# Wifi_Circuit.net
KiCad netlist of a schematic drawn in EAGLE
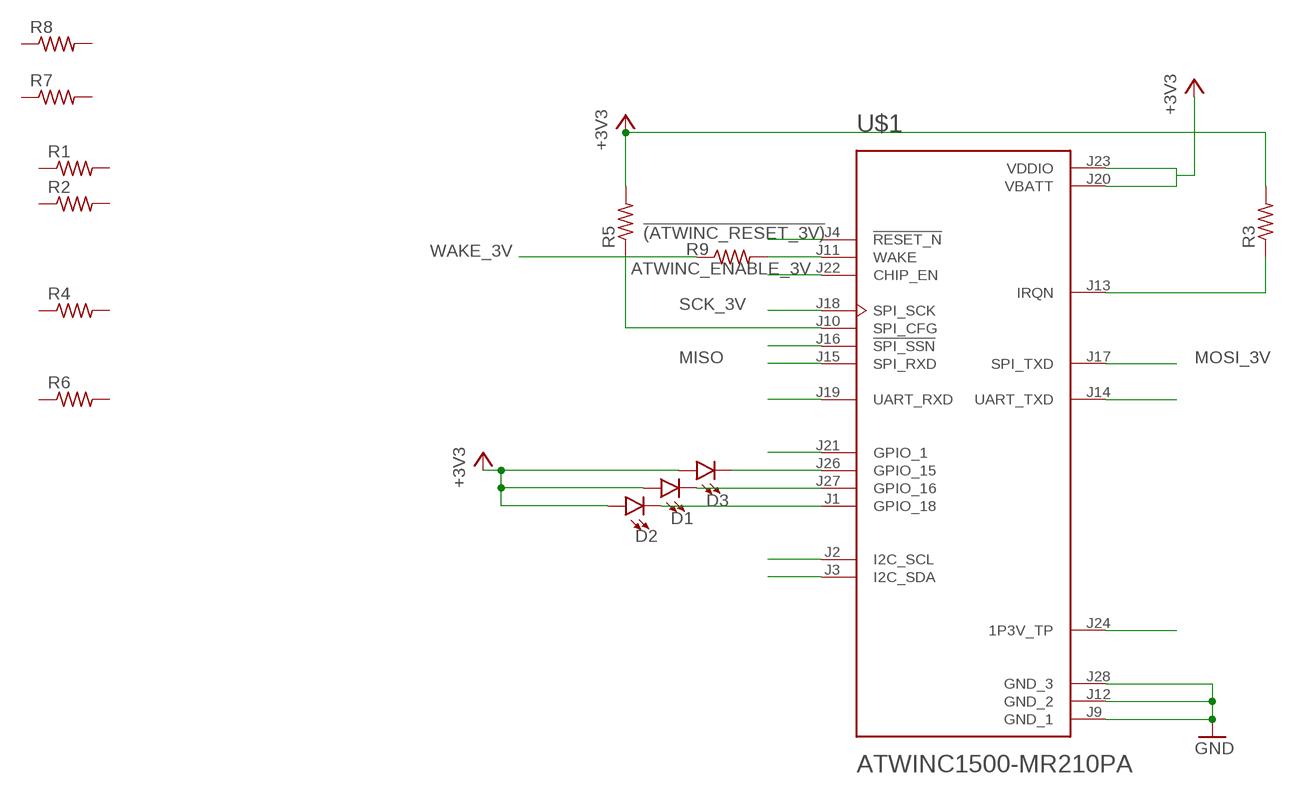
[diagram p0: schematic, sheet 1]

(export (version "E")
  (design (tool "Eeschema 10.0.6"))
  (components
    (comp (ref "D1")
      (value "LED3MM")
      (footprint "eagle-import:LED_3MM")
      (libsource (lib "eagle-import") (part "LED3MM"))
    )
    (comp (ref "D2")
      (value "LED3MM")
      (footprint "eagle-import:LED_3MM")
      (libsource (lib "eagle-import") (part "LED3MM"))
    )
    (comp (ref "D3")
      (value "LED3MM")
      (footprint "eagle-import:LED_3MM")
      (libsource (lib "eagle-import") (part "LED3MM"))
    )
    (comp (ref "R1")
      (value "R-US_R0805")
      (footprint "eagle-import:R0805")
      (libsource (lib "eagle-import") (part "R-US_R0805"))
    )
    (comp (ref "R2")
      (value "R-US_R0805")
      (footprint "eagle-import:R0805")
      (libsource (lib "eagle-import") (part "R-US_R0805"))
    )
    (comp (ref "R3")
      (value "R-US_R0805")
      (footprint "eagle-import:R0805")
      (libsource (lib "eagle-import") (part "R-US_R0805"))
    )
    (comp (ref "R4")
      (value "R-US_R0805")
      (footprint "eagle-import:R0805")
      (libsource (lib "eagle-import") (part "R-US_R0805"))
    )
    (comp (ref "R5")
      (value "R-US_R0805")
      (footprint "eagle-import:R0805")
      (libsource (lib "eagle-import") (part "R-US_R0805"))
    )
    (comp (ref "R6")
      (value "R-US_R0805")
      (footprint "eagle-import:R0805")
      (libsource (lib "eagle-import") (part "R-US_R0805"))
    )
    (comp (ref "R7")
      (value "R-US_R0805")
      (footprint "eagle-import:R0805")
      (libsource (lib "eagle-import") (part "R-US_R0805"))
    )
    (comp (ref "R8")
      (value "R-US_R0805")
      (footprint "eagle-import:R0805")
      (libsource (lib "eagle-import") (part "R-US_R0805"))
    )
    (comp (ref "R9")
      (value "R-US_R0805")
      (footprint "eagle-import:R0805")
      (libsource (lib "eagle-import") (part "R-US_R0805"))
    )
    (comp (ref "U$1")
      (value "ATWINC1500-MR210PA")
      (footprint "eagle-import:ATMEL_ATWINC1500-MR210PA")
      (fields (field (name "MF") "Microchip Technology"))
      (libsource (lib "eagle-import") (part "ATWINC1500-MR210PA"))
    )
  )
  (nets
    (net (code "1") (name "+3V3") (class "Default")
      (node (ref "D1") (pin "A") (pinfunction "A_A") (pintype "passive"))
      (node (ref "D2") (pin "A") (pinfunction "A_A") (pintype "passive"))
      (node (ref "D3") (pin "A") (pinfunction "A_A") (pintype "passive"))
      (node (ref "R3") (pin "2") (pinfunction "2_2") (pintype "passive"))
      (node (ref "R5") (pin "2") (pinfunction "2_2") (pintype "passive"))
      (node (ref "U$1") (pin "J20") (pinfunction "VBATT_J20") (pintype "power_in"))
      (node (ref "U$1") (pin "J23") (pinfunction "VDDIO_J23") (pintype "power_in"))
    )
    (net (code "2") (name "/ATWINC_ENABLE_3V") (class "Default")
      (node (ref "U$1") (pin "J22") (pinfunction "CHIP_EN_J22") (pintype "input"))
    )
    (net (code "3") (name "/MISO") (class "Default")
      (node (ref "U$1") (pin "J15") (pinfunction "SPI_RXD_J15") (pintype "input"))
    )
    (net (code "4") (name "/MOSI_3V") (class "Default")
      (node (ref "U$1") (pin "J17") (pinfunction "SPI_TXD_J17") (pintype "output"))
    )
    (net (code "5") (name "/SCK_3V") (class "Default")
      (node (ref "U$1") (pin "J18") (pinfunction "SPI_SCK_J18") (pintype "input"))
    )
    (net (code "6") (name "/WAKE_3V") (class "Default")
      (node (ref "R9") (pin "1") (pinfunction "1_1") (pintype "passive"))
    )
    (net (code "7") (name "/~{(ATWINC_RESET_3V})") (class "Default")
      (node (ref "U$1") (pin "J4") (pinfunction "~{RESET_N}_J4") (pintype "input"))
    )
    (net (code "8") (name "GND") (class "Default")
      (node (ref "U$1") (pin "J12") (pinfunction "GND_2_J12") (pintype "passive"))
      (node (ref "U$1") (pin "J28") (pinfunction "GND_3_J28") (pintype "passive"))
      (node (ref "U$1") (pin "J9") (pinfunction "GND_1_J9") (pintype "passive"))
    )
    (net (code "9") (name "Net-(D1-C)") (class "Default")
      (node (ref "D1") (pin "K") (pinfunction "C_K") (pintype "passive"))
      (node (ref "U$1") (pin "J27") (pinfunction "GPIO_16_J27") (pintype "bidirectional"))
    )
    (net (code "10") (name "Net-(D2-C)") (class "Default")
      (node (ref "D2") (pin "K") (pinfunction "C_K") (pintype "passive"))
      (node (ref "U$1") (pin "J1") (pinfunction "GPIO_18_J1") (pintype "bidirectional"))
    )
    (net (code "11") (name "Net-(D3-C)") (class "Default")
      (node (ref "D3") (pin "K") (pinfunction "C_K") (pintype "passive"))
      (node (ref "U$1") (pin "J26") (pinfunction "GPIO_15_J26") (pintype "bidirectional"))
    )
    (net (code "12") (name "Net-(U$1-IRQN)") (class "Default")
      (node (ref "R3") (pin "1") (pinfunction "1_1") (pintype "passive"))
      (node (ref "U$1") (pin "J13") (pinfunction "IRQN_J13") (pintype "output"))
    )
    (net (code "13") (name "Net-(U$1-SPI_CFG)") (class "Default")
      (node (ref "R5") (pin "1") (pinfunction "1_1") (pintype "passive"))
      (node (ref "U$1") (pin "J10") (pinfunction "SPI_CFG_J10") (pintype "input"))
    )
    (net (code "14") (name "Net-(U$1-WAKE)") (class "Default")
      (node (ref "R9") (pin "2") (pinfunction "2_2") (pintype "passive"))
      (node (ref "U$1") (pin "J11") (pinfunction "WAKE_J11") (pintype "input"))
    )
    (net (code "15") (name "unconnected-(R1-Pad1)") (class "Default")
      (node (ref "R1") (pin "1") (pinfunction "1_1") (pintype "passive"))
    )
    (net (code "16") (name "unconnected-(R1-Pad2)") (class "Default")
      (node (ref "R1") (pin "2") (pinfunction "2_2") (pintype "passive"))
    )
    (net (code "17") (name "unconnected-(R2-Pad1)") (class "Default")
      (node (ref "R2") (pin "1") (pinfunction "1_1") (pintype "passive"))
    )
    (net (code "18") (name "unconnected-(R2-Pad2)") (class "Default")
      (node (ref "R2") (pin "2") (pinfunction "2_2") (pintype "passive"))
    )
    (net (code "19") (name "unconnected-(R4-Pad1)") (class "Default")
      (node (ref "R4") (pin "1") (pinfunction "1_1") (pintype "passive"))
    )
    (net (code "20") (name "unconnected-(R4-Pad2)") (class "Default")
      (node (ref "R4") (pin "2") (pinfunction "2_2") (pintype "passive"))
    )
    (net (code "21") (name "unconnected-(R6-Pad1)") (class "Default")
      (node (ref "R6") (pin "1") (pinfunction "1_1") (pintype "passive"))
    )
    (net (code "22") (name "unconnected-(R6-Pad2)") (class "Default")
      (node (ref "R6") (pin "2") (pinfunction "2_2") (pintype "passive"))
    )
    (net (code "23") (name "unconnected-(R7-Pad1)") (class "Default")
      (node (ref "R7") (pin "1") (pinfunction "1_1") (pintype "passive"))
    )
    (net (code "24") (name "unconnected-(R7-Pad2)") (class "Default")
      (node (ref "R7") (pin "2") (pinfunction "2_2") (pintype "passive"))
    )
    (net (code "25") (name "unconnected-(R8-Pad1)") (class "Default")
      (node (ref "R8") (pin "1") (pinfunction "1_1") (pintype "passive"))
    )
    (net (code "26") (name "unconnected-(R8-Pad2)") (class "Default")
      (node (ref "R8") (pin "2") (pinfunction "2_2") (pintype "passive"))
    )
    (net (code "27") (name "unconnected-(U$1-1P3V_TP-PadJ24)") (class "Default")
      (node (ref "U$1") (pin "J24") (pinfunction "1P3V_TP_J24") (pintype "passive"))
    )
    (net (code "28") (name "unconnected-(U$1-GPIO_1-PadJ21)") (class "Default")
      (node (ref "U$1") (pin "J21") (pinfunction "GPIO_1_J21") (pintype "bidirectional"))
    )
    (net (code "29") (name "unconnected-(U$1-I2C_SCL-PadJ2)") (class "Default")
      (node (ref "U$1") (pin "J2") (pinfunction "I2C_SCL_J2") (pintype "bidirectional"))
    )
    (net (code "30") (name "unconnected-(U$1-I2C_SDA-PadJ3)") (class "Default")
      (node (ref "U$1") (pin "J3") (pinfunction "I2C_SDA_J3") (pintype "bidirectional"))
    )
    (net (code "31") (name "unconnected-(U$1-UART_RXD-PadJ19)") (class "Default")
      (node (ref "U$1") (pin "J19") (pinfunction "UART_RXD_J19") (pintype "input"))
    )
    (net (code "32") (name "unconnected-(U$1-UART_TXD-PadJ14)") (class "Default")
      (node (ref "U$1") (pin "J14") (pinfunction "UART_TXD_J14") (pintype "output"))
    )
    (net (code "33") (name "unconnected-(U$1-~{SPI_SSN}-PadJ16)") (class "Default")
      (node (ref "U$1") (pin "J16") (pinfunction "~{SPI_SSN}_J16") (pintype "input"))
    )
  )
)
